# lmp9100.net
KiCad netlist of a schematic drawn in EAGLE
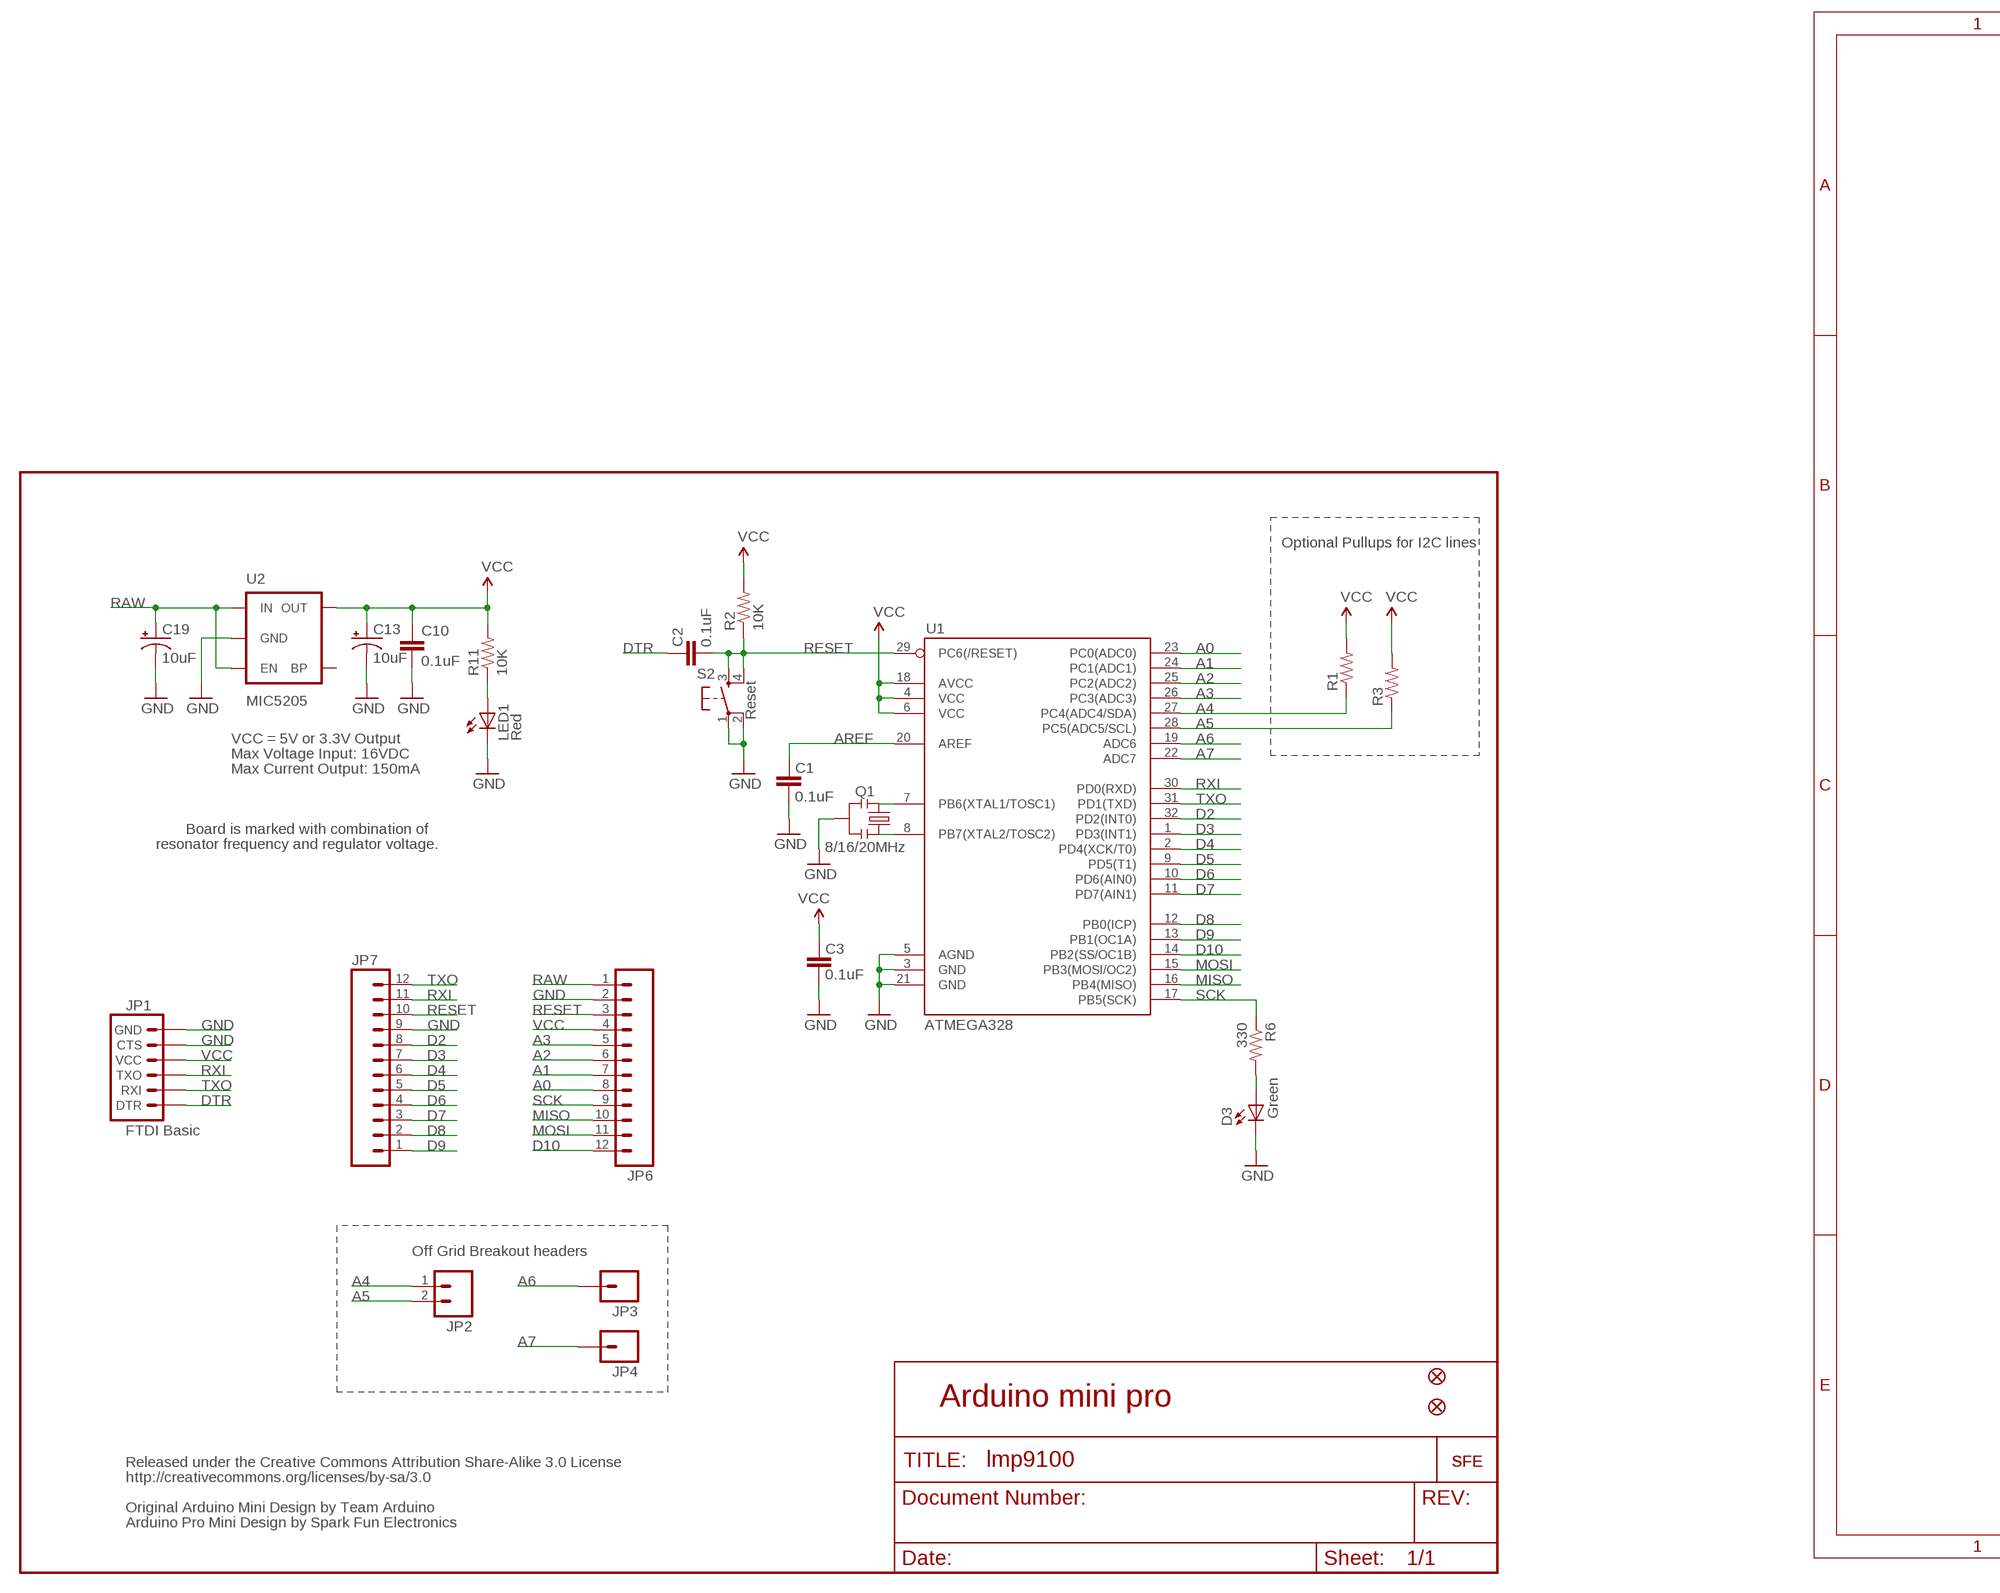
[diagram p0: schematic, sheet 1, part 1 of 2]
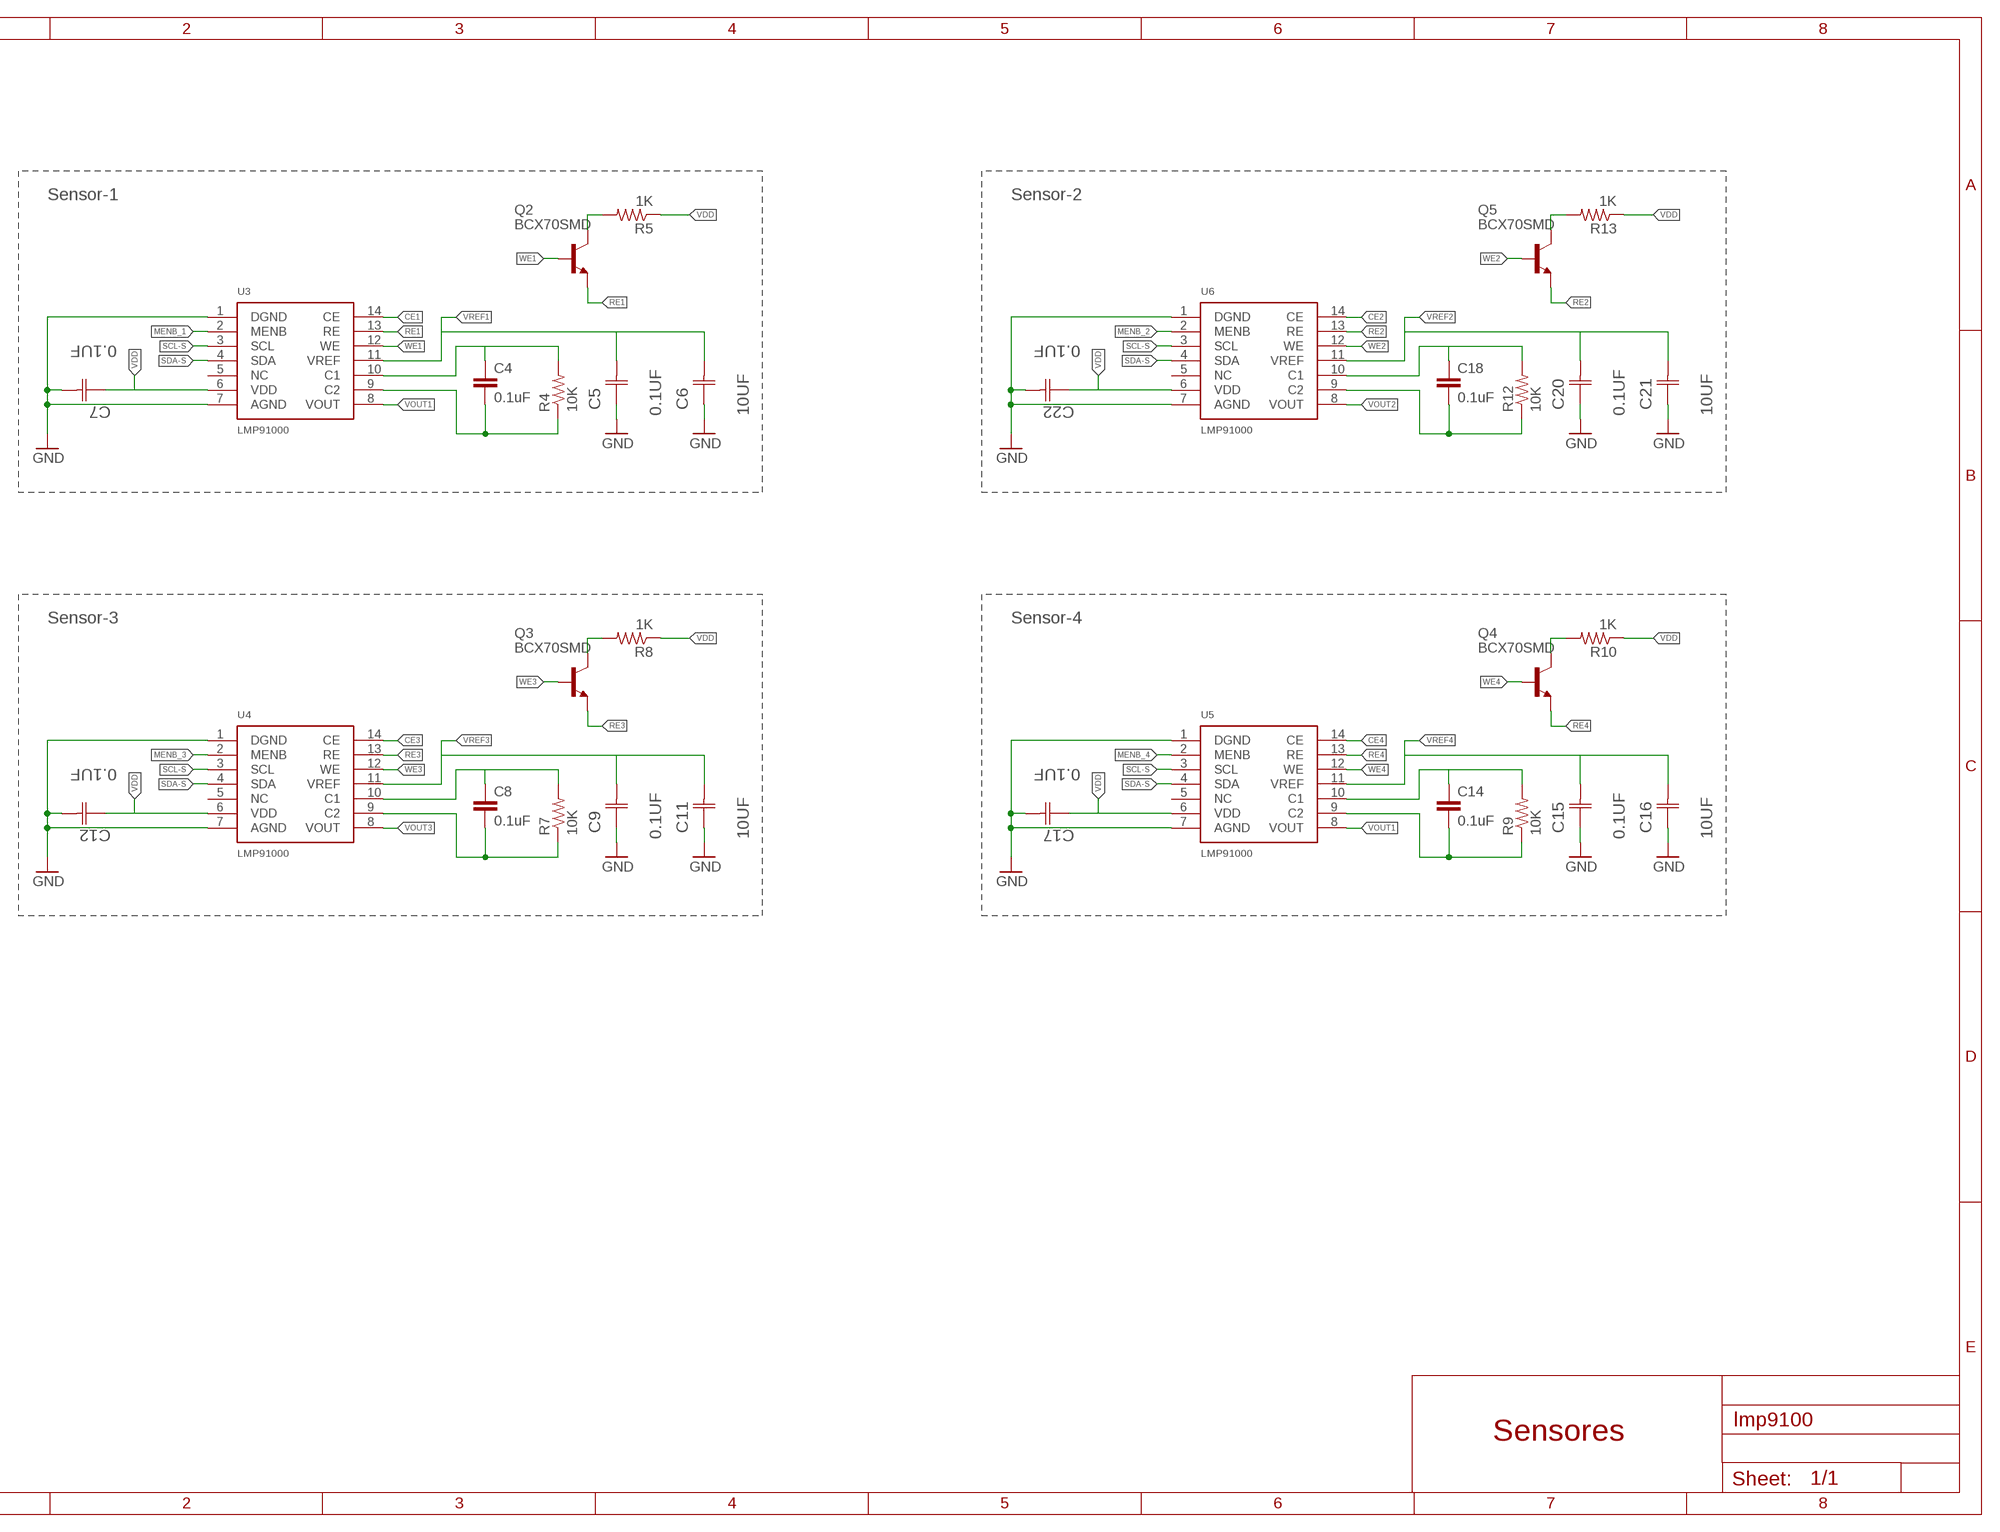
[diagram p1: schematic, sheet 1, part 2 of 2]

(export (version "E")
  (design (tool "Eeschema 10.0.6"))
  (components
    (comp (ref "C1")
      (value "0.1uF")
      (footprint "eagle-import:0402-CAP")
      (libsource (lib "eagle-import") (part "CAP0402-CAP"))
    )
    (comp (ref "C2")
      (value "0.1uF")
      (footprint "eagle-import:0402-CAP")
      (libsource (lib "eagle-import") (part "CAP0402-CAP"))
    )
    (comp (ref "C3")
      (value "0.1uF")
      (footprint "eagle-import:0402-CAP")
      (libsource (lib "eagle-import") (part "CAP0402-CAP"))
    )
    (comp (ref "C4")
      (value "0.1uF")
      (footprint "eagle-import:0402-CAP")
      (libsource (lib "eagle-import") (part "CAP0402-CAP"))
    )
    (comp (ref "C5")
      (value "0.1UF")
      (footprint "eagle-import:CAPC1608X90N")
      (fields (field (name "MPN") "0603YC104KAT2A") (field (name "TOLERANCE") "±10%"))
      (libsource (lib "eagle-import") (part "0603YC104KAT2A"))
    )
    (comp (ref "C6")
      (value "10UF")
      (footprint "eagle-import:CAPC3216X178N")
      (fields (field (name "MPN") "1206YD106MAT2A") (field (name "TOLERANCE") "±20%"))
      (libsource (lib "eagle-import") (part "1206YD106MAT2A"))
    )
    (comp (ref "C7")
      (value "0.1UF")
      (footprint "eagle-import:CAPC1608X90N")
      (fields (field (name "MPN") "0603YC104KAT2A") (field (name "TOLERANCE") "±10%"))
      (libsource (lib "eagle-import") (part "0603YC104KAT2A"))
    )
    (comp (ref "C8")
      (value "0.1uF")
      (footprint "eagle-import:0402-CAP")
      (libsource (lib "eagle-import") (part "CAP0402-CAP"))
    )
    (comp (ref "C9")
      (value "0.1UF")
      (footprint "eagle-import:CAPC1608X90N")
      (fields (field (name "MPN") "0603YC104KAT2A") (field (name "TOLERANCE") "±10%"))
      (libsource (lib "eagle-import") (part "0603YC104KAT2A"))
    )
    (comp (ref "C10")
      (value "0.1uF")
      (footprint "eagle-import:0402-CAP")
      (libsource (lib "eagle-import") (part "CAP0402-CAP"))
    )
    (comp (ref "C11")
      (value "10UF")
      (footprint "eagle-import:CAPC3216X178N")
      (fields (field (name "MPN") "1206YD106MAT2A") (field (name "TOLERANCE") "±20%"))
      (libsource (lib "eagle-import") (part "1206YD106MAT2A"))
    )
    (comp (ref "C12")
      (value "0.1UF")
      (footprint "eagle-import:CAPC1608X90N")
      (fields (field (name "MPN") "0603YC104KAT2A") (field (name "TOLERANCE") "±10%"))
      (libsource (lib "eagle-import") (part "0603YC104KAT2A"))
    )
    (comp (ref "C13")
      (value "10uF")
      (footprint "eagle-import:EIA3216")
      (libsource (lib "eagle-import") (part "CAP_POL1206"))
    )
    (comp (ref "C14")
      (value "0.1uF")
      (footprint "eagle-import:0402-CAP")
      (libsource (lib "eagle-import") (part "CAP0402-CAP"))
    )
    (comp (ref "C15")
      (value "0.1UF")
      (footprint "eagle-import:CAPC1608X90N")
      (fields (field (name "MPN") "0603YC104KAT2A") (field (name "TOLERANCE") "±10%"))
      (libsource (lib "eagle-import") (part "0603YC104KAT2A"))
    )
    (comp (ref "C16")
      (value "10UF")
      (footprint "eagle-import:CAPC3216X178N")
      (fields (field (name "MPN") "1206YD106MAT2A") (field (name "TOLERANCE") "±20%"))
      (libsource (lib "eagle-import") (part "1206YD106MAT2A"))
    )
    (comp (ref "C17")
      (value "0.1UF")
      (footprint "eagle-import:CAPC1608X90N")
      (fields (field (name "MPN") "0603YC104KAT2A") (field (name "TOLERANCE") "±10%"))
      (libsource (lib "eagle-import") (part "0603YC104KAT2A"))
    )
    (comp (ref "C18")
      (value "0.1uF")
      (footprint "eagle-import:0402-CAP")
      (libsource (lib "eagle-import") (part "CAP0402-CAP"))
    )
    (comp (ref "C19")
      (value "10uF")
      (footprint "eagle-import:EIA3216")
      (libsource (lib "eagle-import") (part "CAP_POL1206"))
    )
    (comp (ref "C20")
      (value "0.1UF")
      (footprint "eagle-import:CAPC1608X90N")
      (fields (field (name "MPN") "0603YC104KAT2A") (field (name "TOLERANCE") "±10%"))
      (libsource (lib "eagle-import") (part "0603YC104KAT2A"))
    )
    (comp (ref "C21")
      (value "10UF")
      (footprint "eagle-import:CAPC3216X178N")
      (fields (field (name "MPN") "1206YD106MAT2A") (field (name "TOLERANCE") "±20%"))
      (libsource (lib "eagle-import") (part "1206YD106MAT2A"))
    )
    (comp (ref "C22")
      (value "0.1UF")
      (footprint "eagle-import:CAPC1608X90N")
      (fields (field (name "MPN") "0603YC104KAT2A") (field (name "TOLERANCE") "±10%"))
      (libsource (lib "eagle-import") (part "0603YC104KAT2A"))
    )
    (comp (ref "D3")
      (value "Green")
      (footprint "eagle-import:LED-0603")
      (libsource (lib "eagle-import") (part "LED0603"))
    )
    (comp (ref "JP1")
      (value "FTDI Basic")
      (footprint "eagle-import:1X06")
      (libsource (lib "eagle-import") (part "ARDUINO_SERIAL_PROGRAMPTH"))
    )
    (comp (ref "JP2")
      (value "M02PTH")
      (footprint "eagle-import:1X02")
      (libsource (lib "eagle-import") (part "M02PTH"))
    )
    (comp (ref "JP3")
      (value "M01PTH")
      (footprint "eagle-import:1X01")
      (libsource (lib "eagle-import") (part "M01PTH"))
    )
    (comp (ref "JP4")
      (value "M01PTH")
      (footprint "eagle-import:1X01")
      (libsource (lib "eagle-import") (part "M01PTH"))
    )
    (comp (ref "JP5")
      (value "FIDUCIALUFIDUCIAL")
      (footprint "eagle-import:MICRO-FIDUCIAL")
      (libsource (lib "eagle-import") (part "FIDUCIALUFIDUCIAL"))
    )
    (comp (ref "JP6")
      (value "M12PTH")
      (footprint "eagle-import:1X12")
      (libsource (lib "eagle-import") (part "M12PTH"))
    )
    (comp (ref "JP7")
      (value "M12PTH")
      (footprint "eagle-import:1X12")
      (libsource (lib "eagle-import") (part "M12PTH"))
    )
    (comp (ref "JP8")
      (value "FIDUCIALUFIDUCIAL")
      (footprint "eagle-import:MICRO-FIDUCIAL")
      (libsource (lib "eagle-import") (part "FIDUCIALUFIDUCIAL"))
    )
    (comp (ref "LED1")
      (value "Red")
      (footprint "eagle-import:LED-0603")
      (libsource (lib "eagle-import") (part "LED0603"))
    )
    (comp (ref "Q1")
      (value "8/16/20MHz")
      (footprint "eagle-import:RESONATOR-SMD")
      (libsource (lib "eagle-import") (part "RESONATORSMD"))
    )
    (comp (ref "Q2")
      (value "BCX70SMD")
      (footprint "eagle-import:SOT23")
      (libsource (lib "eagle-import") (part "BCX70SMD"))
    )
    (comp (ref "Q3")
      (value "BCX70SMD")
      (footprint "eagle-import:SOT23")
      (libsource (lib "eagle-import") (part "BCX70SMD"))
    )
    (comp (ref "Q4")
      (value "BCX70SMD")
      (footprint "eagle-import:SOT23")
      (libsource (lib "eagle-import") (part "BCX70SMD"))
    )
    (comp (ref "Q5")
      (value "BCX70SMD")
      (footprint "eagle-import:SOT23")
      (libsource (lib "eagle-import") (part "BCX70SMD"))
    )
    (comp (ref "R1")
      (value "RESISTOR0402-RES")
      (footprint "eagle-import:0402-RES")
      (libsource (lib "eagle-import") (part "RESISTOR0402-RES"))
    )
    (comp (ref "R2")
      (value "10K")
      (footprint "eagle-import:0402-RES")
      (libsource (lib "eagle-import") (part "RESISTOR0402-RES"))
    )
    (comp (ref "R3")
      (value "RESISTOR0402-RES")
      (footprint "eagle-import:0402-RES")
      (libsource (lib "eagle-import") (part "RESISTOR0402-RES"))
    )
    (comp (ref "R4")
      (value "10K")
      (footprint "eagle-import:0402-RES")
      (libsource (lib "eagle-import") (part "RESISTOR0402-RES"))
    )
    (comp (ref "R5")
      (value "1K")
      (footprint "eagle-import:0402-RES")
      (libsource (lib "eagle-import") (part "RESISTOR0402-RES"))
    )
    (comp (ref "R6")
      (value "330")
      (footprint "eagle-import:0402-RES")
      (libsource (lib "eagle-import") (part "RESISTOR0402-RES"))
    )
    (comp (ref "R7")
      (value "10K")
      (footprint "eagle-import:0402-RES")
      (libsource (lib "eagle-import") (part "RESISTOR0402-RES"))
    )
    (comp (ref "R8")
      (value "1K")
      (footprint "eagle-import:0402-RES")
      (libsource (lib "eagle-import") (part "RESISTOR0402-RES"))
    )
    (comp (ref "R9")
      (value "10K")
      (footprint "eagle-import:0402-RES")
      (libsource (lib "eagle-import") (part "RESISTOR0402-RES"))
    )
    (comp (ref "R10")
      (value "1K")
      (footprint "eagle-import:0402-RES")
      (libsource (lib "eagle-import") (part "RESISTOR0402-RES"))
    )
    (comp (ref "R11")
      (value "10K")
      (footprint "eagle-import:0402-RES")
      (libsource (lib "eagle-import") (part "RESISTOR0402-RES"))
    )
    (comp (ref "R12")
      (value "10K")
      (footprint "eagle-import:0402-RES")
      (libsource (lib "eagle-import") (part "RESISTOR0402-RES"))
    )
    (comp (ref "R13")
      (value "1K")
      (footprint "eagle-import:0402-RES")
      (libsource (lib "eagle-import") (part "RESISTOR0402-RES"))
    )
    (comp (ref "S2")
      (value "Reset")
      (footprint "eagle-import:TACTILE_SWITCH_SMD")
      (libsource (lib "eagle-import") (part "TAC_SWITCHSMD"))
    )
    (comp (ref "U$1")
      (value "LOGO-SFESK")
      (footprint "eagle-import:SFE-LOGO-FLAME")
      (libsource (lib "eagle-import") (part "LOGO-SFESK"))
    )
    (comp (ref "U$11")
      (value "LOGO-SFENEW")
      (footprint "eagle-import:SFE-NEW-WEBLOGO")
      (libsource (lib "eagle-import") (part "LOGO-SFENEW"))
    )
    (comp (ref "U1")
      (value "ATMEGA328")
      (footprint "eagle-import:TQFP32-08")
      (libsource (lib "eagle-import") (part "ATMEGA168"))
    )
    (comp (ref "U2")
      (value "MIC5205")
      (footprint "eagle-import:SOT23-5")
      (libsource (lib "eagle-import") (part "V_REG_LDOSMD"))
    )
    (comp (ref "U3")
      (value "LMP91000")
      (footprint "eagle-import:LMP91000")
      (libsource (lib "eagle-import") (part "LMP91000"))
    )
    (comp (ref "U4")
      (value "LMP91000")
      (footprint "eagle-import:LMP91000")
      (libsource (lib "eagle-import") (part "LMP91000"))
    )
    (comp (ref "U5")
      (value "LMP91000")
      (footprint "eagle-import:LMP91000")
      (libsource (lib "eagle-import") (part "LMP91000"))
    )
    (comp (ref "U6")
      (value "LMP91000")
      (footprint "eagle-import:LMP91000")
      (libsource (lib "eagle-import") (part "LMP91000"))
    )
  )
  (nets
    (net (code "1") (name "/A0") (class "Default")
      (node (ref "JP6") (pin "8") (pinfunction "8_8") (pintype "passive"))
      (node (ref "U1") (pin "23") (pinfunction "PC0(ADC0)_23") (pintype "bidirectional"))
    )
    (net (code "2") (name "/A1") (class "Default")
      (node (ref "JP6") (pin "7") (pinfunction "7_7") (pintype "passive"))
      (node (ref "U1") (pin "24") (pinfunction "PC1(ADC1)_24") (pintype "bidirectional"))
    )
    (net (code "3") (name "/A2") (class "Default")
      (node (ref "JP6") (pin "6") (pinfunction "6_6") (pintype "passive"))
      (node (ref "U1") (pin "25") (pinfunction "PC2(ADC2)_25") (pintype "bidirectional"))
    )
    (net (code "4") (name "/A3") (class "Default")
      (node (ref "JP6") (pin "5") (pinfunction "5_5") (pintype "passive"))
      (node (ref "U1") (pin "26") (pinfunction "PC3(ADC3)_26") (pintype "bidirectional"))
    )
    (net (code "5") (name "/A4") (class "Default")
      (node (ref "JP2") (pin "1") (pinfunction "1_1") (pintype "passive"))
      (node (ref "R1") (pin "1") (pinfunction "1_1") (pintype "passive"))
      (node (ref "U1") (pin "27") (pinfunction "PC4(ADC4/SDA)_27") (pintype "bidirectional"))
    )
    (net (code "6") (name "/A5") (class "Default")
      (node (ref "JP2") (pin "2") (pinfunction "2_2") (pintype "passive"))
      (node (ref "R3") (pin "1") (pinfunction "1_1") (pintype "passive"))
      (node (ref "U1") (pin "28") (pinfunction "PC5(ADC5/SCL)_28") (pintype "bidirectional"))
    )
    (net (code "7") (name "/A6") (class "Default")
      (node (ref "JP3") (pin "1") (pinfunction "1_1") (pintype "passive"))
      (node (ref "U1") (pin "19") (pinfunction "ADC6_19") (pintype "bidirectional"))
    )
    (net (code "8") (name "/A7") (class "Default")
      (node (ref "JP4") (pin "1") (pinfunction "1_1") (pintype "passive"))
      (node (ref "U1") (pin "22") (pinfunction "ADC7_22") (pintype "bidirectional"))
    )
    (net (code "9") (name "/AREF") (class "Default")
      (node (ref "C1") (pin "2") (pinfunction "2_2") (pintype "passive"))
      (node (ref "U1") (pin "20") (pinfunction "AREF_20") (pintype "bidirectional"))
    )
    (net (code "10") (name "/D2") (class "Default")
      (node (ref "JP7") (pin "8") (pinfunction "8_8") (pintype "passive"))
      (node (ref "U1") (pin "32") (pinfunction "PD2(INT0)_32") (pintype "bidirectional"))
    )
    (net (code "11") (name "/D3") (class "Default")
      (node (ref "JP7") (pin "7") (pinfunction "7_7") (pintype "passive"))
      (node (ref "U1") (pin "1") (pinfunction "PD3(INT1)_1") (pintype "bidirectional"))
    )
    (net (code "12") (name "/D4") (class "Default")
      (node (ref "JP7") (pin "6") (pinfunction "6_6") (pintype "passive"))
      (node (ref "U1") (pin "2") (pinfunction "PD4(XCK/T0)_2") (pintype "bidirectional"))
    )
    (net (code "13") (name "/D5") (class "Default")
      (node (ref "JP7") (pin "5") (pinfunction "5_5") (pintype "passive"))
      (node (ref "U1") (pin "9") (pinfunction "PD5(T1)_9") (pintype "bidirectional"))
    )
    (net (code "14") (name "/D6") (class "Default")
      (node (ref "JP7") (pin "4") (pinfunction "4_4") (pintype "passive"))
      (node (ref "U1") (pin "10") (pinfunction "PD6(AIN0)_10") (pintype "bidirectional"))
    )
    (net (code "15") (name "/D7") (class "Default")
      (node (ref "JP7") (pin "3") (pinfunction "3_3") (pintype "passive"))
      (node (ref "U1") (pin "11") (pinfunction "PD7(AIN1)_11") (pintype "bidirectional"))
    )
    (net (code "16") (name "/D8") (class "Default")
      (node (ref "JP7") (pin "2") (pinfunction "2_2") (pintype "passive"))
      (node (ref "U1") (pin "12") (pinfunction "PB0(ICP)_12") (pintype "bidirectional"))
    )
    (net (code "17") (name "/D9") (class "Default")
      (node (ref "JP7") (pin "1") (pinfunction "1_1") (pintype "passive"))
      (node (ref "U1") (pin "13") (pinfunction "PB1(OC1A)_13") (pintype "bidirectional"))
    )
    (net (code "18") (name "/D10") (class "Default")
      (node (ref "JP6") (pin "12") (pinfunction "12_12") (pintype "passive"))
      (node (ref "U1") (pin "14") (pinfunction "PB2(SS/OC1B)_14") (pintype "bidirectional"))
    )
    (net (code "19") (name "/DTR") (class "Default")
      (node (ref "C2") (pin "2") (pinfunction "2_2") (pintype "passive"))
      (node (ref "JP1") (pin "1") (pinfunction "DTR_1") (pintype "passive"))
    )
    (net (code "20") (name "/MISO") (class "Default")
      (node (ref "JP6") (pin "10") (pinfunction "10_10") (pintype "passive"))
      (node (ref "U1") (pin "16") (pinfunction "PB4(MISO)_16") (pintype "bidirectional"))
    )
    (net (code "21") (name "/MOSI") (class "Default")
      (node (ref "JP6") (pin "11") (pinfunction "11_11") (pintype "passive"))
      (node (ref "U1") (pin "15") (pinfunction "PB3(MOSI/OC2)_15") (pintype "bidirectional"))
    )
    (net (code "22") (name "/RAW") (class "Default")
      (node (ref "C19") (pin "A") (pinfunction "+_A") (pintype "passive"))
      (node (ref "JP6") (pin "1") (pinfunction "1_1") (pintype "passive"))
      (node (ref "U2") (pin "1") (pinfunction "IN_1") (pintype "input"))
      (node (ref "U2") (pin "3") (pinfunction "EN_3") (pintype "input"))
    )
    (net (code "23") (name "/RESET") (class "Default")
      (node (ref "C2") (pin "1") (pinfunction "1_1") (pintype "passive"))
      (node (ref "JP6") (pin "3") (pinfunction "3_3") (pintype "passive"))
      (node (ref "JP7") (pin "10") (pinfunction "10_10") (pintype "passive"))
      (node (ref "R2") (pin "1") (pinfunction "1_1") (pintype "passive"))
      (node (ref "S2") (pin "3") (pinfunction "3_3") (pintype "passive"))
      (node (ref "S2") (pin "4") (pinfunction "4_4") (pintype "passive"))
      (node (ref "U1") (pin "29") (pinfunction "PC6(/RESET)_29") (pintype "bidirectional"))
    )
    (net (code "24") (name "/RXI") (class "Default")
      (node (ref "JP1") (pin "3") (pinfunction "TXO_3") (pintype "passive"))
      (node (ref "JP7") (pin "11") (pinfunction "11_11") (pintype "passive"))
      (node (ref "U1") (pin "30") (pinfunction "PD0(RXD)_30") (pintype "bidirectional"))
    )
    (net (code "25") (name "/SCK") (class "Default")
      (node (ref "JP6") (pin "9") (pinfunction "9_9") (pintype "passive"))
      (node (ref "R6") (pin "1") (pinfunction "1_1") (pintype "passive"))
      (node (ref "U1") (pin "17") (pinfunction "PB5(SCK)_17") (pintype "bidirectional"))
    )
    (net (code "26") (name "/TXO") (class "Default")
      (node (ref "JP1") (pin "2") (pinfunction "RXI_2") (pintype "passive"))
      (node (ref "JP7") (pin "12") (pinfunction "12_12") (pintype "passive"))
      (node (ref "U1") (pin "31") (pinfunction "PD1(TXD)_31") (pintype "bidirectional"))
    )
    (net (code "27") (name "CE1") (class "Default")
      (node (ref "U3") (pin "14") (pinfunction "CE_14") (pintype "bidirectional"))
    )
    (net (code "28") (name "CE2") (class "Default")
      (node (ref "U6") (pin "14") (pinfunction "CE_14") (pintype "bidirectional"))
    )
    (net (code "29") (name "CE3") (class "Default")
      (node (ref "U4") (pin "14") (pinfunction "CE_14") (pintype "bidirectional"))
    )
    (net (code "30") (name "CE4") (class "Default")
      (node (ref "U5") (pin "14") (pinfunction "CE_14") (pintype "bidirectional"))
    )
    (net (code "31") (name "GND") (class "Default")
      (node (ref "C1") (pin "1") (pinfunction "1_1") (pintype "passive"))
      (node (ref "C10") (pin "2") (pinfunction "2_2") (pintype "passive"))
      (node (ref "C11") (pin "1") (pinfunction "C1_1") (pintype "passive"))
      (node (ref "C12") (pin "2") (pinfunction "C2_2") (pintype "passive"))
      (node (ref "C13") (pin "C") (pinfunction "-_C") (pintype "passive"))
      (node (ref "C15") (pin "1") (pinfunction "C1_1") (pintype "passive"))
      (node (ref "C16") (pin "1") (pinfunction "C1_1") (pintype "passive"))
      (node (ref "C17") (pin "2") (pinfunction "C2_2") (pintype "passive"))
      (node (ref "C19") (pin "C") (pinfunction "-_C") (pintype "passive"))
      (node (ref "C20") (pin "1") (pinfunction "C1_1") (pintype "passive"))
      (node (ref "C21") (pin "1") (pinfunction "C1_1") (pintype "passive"))
      (node (ref "C22") (pin "2") (pinfunction "C2_2") (pintype "passive"))
      (node (ref "C3") (pin "1") (pinfunction "1_1") (pintype "passive"))
      (node (ref "C5") (pin "1") (pinfunction "C1_1") (pintype "passive"))
      (node (ref "C6") (pin "1") (pinfunction "C1_1") (pintype "passive"))
      (node (ref "C7") (pin "2") (pinfunction "C2_2") (pintype "passive"))
      (node (ref "C9") (pin "1") (pinfunction "C1_1") (pintype "passive"))
      (node (ref "D3") (pin "C") (pinfunction "C_C") (pintype "passive"))
      (node (ref "JP1") (pin "5") (pinfunction "CTS_5") (pintype "passive"))
      (node (ref "JP1") (pin "6") (pinfunction "GND_6") (pintype "passive"))
      (node (ref "JP6") (pin "2") (pinfunction "2_2") (pintype "passive"))
      (node (ref "JP7") (pin "9") (pinfunction "9_9") (pintype "passive"))
      (node (ref "LED1") (pin "C") (pinfunction "C_C") (pintype "passive"))
      (node (ref "Q1") (pin "2") (pinfunction "2_2") (pintype "passive"))
      (node (ref "S2") (pin "1") (pinfunction "1_1") (pintype "passive"))
      (node (ref "S2") (pin "2") (pinfunction "2_2") (pintype "passive"))
      (node (ref "U1") (pin "21") (pinfunction "GND_21") (pintype "bidirectional"))
      (node (ref "U1") (pin "3") (pinfunction "GND_3") (pintype "bidirectional"))
      (node (ref "U1") (pin "5") (pinfunction "AGND_5") (pintype "bidirectional"))
      (node (ref "U2") (pin "2") (pinfunction "GND_2") (pintype "input"))
      (node (ref "U3") (pin "1") (pinfunction "DGND_1") (pintype "bidirectional"))
      (node (ref "U3") (pin "7") (pinfunction "AGND_7") (pintype "bidirectional"))
      (node (ref "U4") (pin "1") (pinfunction "DGND_1") (pintype "bidirectional"))
      (node (ref "U4") (pin "7") (pinfunction "AGND_7") (pintype "bidirectional"))
      (node (ref "U5") (pin "1") (pinfunction "DGND_1") (pintype "bidirectional"))
      (node (ref "U5") (pin "7") (pinfunction "AGND_7") (pintype "bidirectional"))
      (node (ref "U6") (pin "1") (pinfunction "DGND_1") (pintype "bidirectional"))
      (node (ref "U6") (pin "7") (pinfunction "AGND_7") (pintype "bidirectional"))
    )
    (net (code "32") (name "MENB_1") (class "Default")
      (node (ref "U3") (pin "2") (pinfunction "MENB_2") (pintype "bidirectional"))
    )
    (net (code "33") (name "MENB_2") (class "Default")
      (node (ref "U6") (pin "2") (pinfunction "MENB_2") (pintype "bidirectional"))
    )
    (net (code "34") (name "MENB_3") (class "Default")
      (node (ref "U4") (pin "2") (pinfunction "MENB_2") (pintype "bidirectional"))
    )
    (net (code "35") (name "MENB_4") (class "Default")
      (node (ref "U5") (pin "2") (pinfunction "MENB_2") (pintype "bidirectional"))
    )
    (net (code "36") (name "Net-(D3-PadA)") (class "Default")
      (node (ref "D3") (pin "A") (pinfunction "A_A") (pintype "passive"))
      (node (ref "R6") (pin "2") (pinfunction "2_2") (pintype "passive"))
    )
    (net (code "37") (name "Net-(LED1-PadA)") (class "Default")
      (node (ref "LED1") (pin "A") (pinfunction "A_A") (pintype "passive"))
      (node (ref "R11") (pin "1") (pinfunction "1_1") (pintype "passive"))
    )
    (net (code "38") (name "Net-(Q2-C)") (class "Default")
      (node (ref "Q2") (pin "3") (pinfunction "C_3") (pintype "passive"))
      (node (ref "R5") (pin "2") (pinfunction "2_2") (pintype "passive"))
    )
    (net (code "39") (name "Net-(Q3-C)") (class "Default")
      (node (ref "Q3") (pin "3") (pinfunction "C_3") (pintype "passive"))
      (node (ref "R8") (pin "2") (pinfunction "2_2") (pintype "passive"))
    )
    (net (code "40") (name "Net-(Q4-C)") (class "Default")
      (node (ref "Q4") (pin "3") (pinfunction "C_3") (pintype "passive"))
      (node (ref "R10") (pin "2") (pinfunction "2_2") (pintype "passive"))
    )
    (net (code "41") (name "Net-(Q5-C)") (class "Default")
      (node (ref "Q5") (pin "3") (pinfunction "C_3") (pintype "passive"))
      (node (ref "R13") (pin "2") (pinfunction "2_2") (pintype "passive"))
    )
    (net (code "42") (name "Net-(U1-PB6(XTAL1{slash}TOSC1))") (class "Default")
      (node (ref "Q1") (pin "3") (pinfunction "3_3") (pintype "passive"))
      (node (ref "U1") (pin "7") (pinfunction "PB6(XTAL1/TOSC1)_7") (pintype "bidirectional"))
    )
    (net (code "43") (name "Net-(U1-PB7(XTAL2{slash}TOSC2))") (class "Default")
      (node (ref "Q1") (pin "1") (pinfunction "1_1") (pintype "passive"))
      (node (ref "U1") (pin "8") (pinfunction "PB7(XTAL2/TOSC2)_8") (pintype "bidirectional"))
    )
    (net (code "44") (name "Net-(U3-C1)") (class "Default")
      (node (ref "C4") (pin "1") (pinfunction "1_1") (pintype "passive"))
      (node (ref "R4") (pin "2") (pinfunction "2_2") (pintype "passive"))
      (node (ref "U3") (pin "10") (pinfunction "C1_10") (pintype "bidirectional"))
    )
    (net (code "45") (name "Net-(U3-C2)") (class "Default")
      (node (ref "C4") (pin "2") (pinfunction "2_2") (pintype "passive"))
      (node (ref "R4") (pin "1") (pinfunction "1_1") (pintype "passive"))
      (node (ref "U3") (pin "9") (pinfunction "C2_9") (pintype "bidirectional"))
    )
    (net (code "46") (name "Net-(U4-C1)") (class "Default")
      (node (ref "C8") (pin "1") (pinfunction "1_1") (pintype "passive"))
      (node (ref "R7") (pin "2") (pinfunction "2_2") (pintype "passive"))
      (node (ref "U4") (pin "10") (pinfunction "C1_10") (pintype "bidirectional"))
    )
    (net (code "47") (name "Net-(U4-C2)") (class "Default")
      (node (ref "C8") (pin "2") (pinfunction "2_2") (pintype "passive"))
      (node (ref "R7") (pin "1") (pinfunction "1_1") (pintype "passive"))
      (node (ref "U4") (pin "9") (pinfunction "C2_9") (pintype "bidirectional"))
    )
    (net (code "48") (name "Net-(U5-C1)") (class "Default")
      (node (ref "C14") (pin "1") (pinfunction "1_1") (pintype "passive"))
      (node (ref "R9") (pin "2") (pinfunction "2_2") (pintype "passive"))
      (node (ref "U5") (pin "10") (pinfunction "C1_10") (pintype "bidirectional"))
    )
    (net (code "49") (name "Net-(U5-C2)") (class "Default")
      (node (ref "C14") (pin "2") (pinfunction "2_2") (pintype "passive"))
      (node (ref "R9") (pin "1") (pinfunction "1_1") (pintype "passive"))
      (node (ref "U5") (pin "9") (pinfunction "C2_9") (pintype "bidirectional"))
    )
    (net (code "50") (name "Net-(U6-C1)") (class "Default")
      (node (ref "C18") (pin "1") (pinfunction "1_1") (pintype "passive"))
      (node (ref "R12") (pin "2") (pinfunction "2_2") (pintype "passive"))
      (node (ref "U6") (pin "10") (pinfunction "C1_10") (pintype "bidirectional"))
    )
    (net (code "51") (name "Net-(U6-C2)") (class "Default")
      (node (ref "C18") (pin "2") (pinfunction "2_2") (pintype "passive"))
      (node (ref "R12") (pin "1") (pinfunction "1_1") (pintype "passive"))
      (node (ref "U6") (pin "9") (pinfunction "C2_9") (pintype "bidirectional"))
    )
    (net (code "52") (name "RE1") (class "Default")
      (node (ref "Q2") (pin "2") (pinfunction "E_2") (pintype "passive"))
      (node (ref "U3") (pin "13") (pinfunction "RE_13") (pintype "bidirectional"))
    )
    (net (code "53") (name "RE2") (class "Default")
      (node (ref "Q5") (pin "2") (pinfunction "E_2") (pintype "passive"))
      (node (ref "U6") (pin "13") (pinfunction "RE_13") (pintype "bidirectional"))
    )
    (net (code "54") (name "RE3") (class "Default")
      (node (ref "Q3") (pin "2") (pinfunction "E_2") (pintype "passive"))
      (node (ref "U4") (pin "13") (pinfunction "RE_13") (pintype "bidirectional"))
    )
    (net (code "55") (name "RE4") (class "Default")
      (node (ref "Q4") (pin "2") (pinfunction "E_2") (pintype "passive"))
      (node (ref "U5") (pin "13") (pinfunction "RE_13") (pintype "bidirectional"))
    )
    (net (code "56") (name "SCL-S") (class "Default")
      (node (ref "U3") (pin "3") (pinfunction "SCL_3") (pintype "bidirectional"))
      (node (ref "U4") (pin "3") (pinfunction "SCL_3") (pintype "bidirectional"))
      (node (ref "U5") (pin "3") (pinfunction "SCL_3") (pintype "bidirectional"))
      (node (ref "U6") (pin "3") (pinfunction "SCL_3") (pintype "bidirectional"))
    )
    (net (code "57") (name "SDA-S") (class "Default")
      (node (ref "U3") (pin "4") (pinfunction "SDA_4") (pintype "bidirectional"))
      (node (ref "U4") (pin "4") (pinfunction "SDA_4") (pintype "bidirectional"))
      (node (ref "U5") (pin "4") (pinfunction "SDA_4") (pintype "bidirectional"))
      (node (ref "U6") (pin "4") (pinfunction "SDA_4") (pintype "bidirectional"))
    )
    (net (code "58") (name "VCC") (class "Default")
      (node (ref "C10") (pin "1") (pinfunction "1_1") (pintype "passive"))
      (node (ref "C13") (pin "A") (pinfunction "+_A") (pintype "passive"))
      (node (ref "C3") (pin "2") (pinfunction "2_2") (pintype "passive"))
      (node (ref "JP1") (pin "4") (pinfunction "VCC_4") (pintype "passive"))
      (node (ref "JP6") (pin "4") (pinfunction "4_4") (pintype "passive"))
      (node (ref "R1") (pin "2") (pinfunction "2_2") (pintype "passive"))
      (node (ref "R11") (pin "2") (pinfunction "2_2") (pintype "passive"))
      (node (ref "R2") (pin "2") (pinfunction "2_2") (pintype "passive"))
      (node (ref "R3") (pin "2") (pinfunction "2_2") (pintype "passive"))
      (node (ref "U1") (pin "18") (pinfunction "AVCC_18") (pintype "bidirectional"))
      (node (ref "U1") (pin "4") (pinfunction "VCC_4") (pintype "bidirectional"))
      (node (ref "U1") (pin "6") (pinfunction "VCC_6") (pintype "bidirectional"))
      (node (ref "U2") (pin "5") (pinfunction "OUT_5") (pintype "passive"))
    )
    (net (code "59") (name "VDD") (class "Default")
      (node (ref "C12") (pin "1") (pinfunction "C1_1") (pintype "passive"))
      (node (ref "C17") (pin "1") (pinfunction "C1_1") (pintype "passive"))
      (node (ref "C22") (pin "1") (pinfunction "C1_1") (pintype "passive"))
      (node (ref "C7") (pin "1") (pinfunction "C1_1") (pintype "passive"))
      (node (ref "R10") (pin "1") (pinfunction "1_1") (pintype "passive"))
      (node (ref "R13") (pin "1") (pinfunction "1_1") (pintype "passive"))
      (node (ref "R5") (pin "1") (pinfunction "1_1") (pintype "passive"))
      (node (ref "R8") (pin "1") (pinfunction "1_1") (pintype "passive"))
      (node (ref "U3") (pin "6") (pinfunction "VDD_6") (pintype "bidirectional"))
      (node (ref "U4") (pin "6") (pinfunction "VDD_6") (pintype "bidirectional"))
      (node (ref "U5") (pin "6") (pinfunction "VDD_6") (pintype "bidirectional"))
      (node (ref "U6") (pin "6") (pinfunction "VDD_6") (pintype "bidirectional"))
    )
    (net (code "60") (name "VOUT1") (class "Default")
      (node (ref "U3") (pin "8") (pinfunction "VOUT_8") (pintype "bidirectional"))
      (node (ref "U5") (pin "8") (pinfunction "VOUT_8") (pintype "bidirectional"))
    )
    (net (code "61") (name "VOUT2") (class "Default")
      (node (ref "U6") (pin "8") (pinfunction "VOUT_8") (pintype "bidirectional"))
    )
    (net (code "62") (name "VOUT3") (class "Default")
      (node (ref "U4") (pin "8") (pinfunction "VOUT_8") (pintype "bidirectional"))
    )
    (net (code "63") (name "VREF1") (class "Default")
      (node (ref "C5") (pin "2") (pinfunction "C2_2") (pintype "passive"))
      (node (ref "C6") (pin "2") (pinfunction "C2_2") (pintype "passive"))
      (node (ref "U3") (pin "11") (pinfunction "VREF_11") (pintype "bidirectional"))
    )
    (net (code "64") (name "VREF2") (class "Default")
      (node (ref "C20") (pin "2") (pinfunction "C2_2") (pintype "passive"))
      (node (ref "C21") (pin "2") (pinfunction "C2_2") (pintype "passive"))
      (node (ref "U6") (pin "11") (pinfunction "VREF_11") (pintype "bidirectional"))
    )
    (net (code "65") (name "VREF3") (class "Default")
      (node (ref "C11") (pin "2") (pinfunction "C2_2") (pintype "passive"))
      (node (ref "C9") (pin "2") (pinfunction "C2_2") (pintype "passive"))
      (node (ref "U4") (pin "11") (pinfunction "VREF_11") (pintype "bidirectional"))
    )
    (net (code "66") (name "VREF4") (class "Default")
      (node (ref "C15") (pin "2") (pinfunction "C2_2") (pintype "passive"))
      (node (ref "C16") (pin "2") (pinfunction "C2_2") (pintype "passive"))
      (node (ref "U5") (pin "11") (pinfunction "VREF_11") (pintype "bidirectional"))
    )
    (net (code "67") (name "WE1") (class "Default")
      (node (ref "Q2") (pin "1") (pinfunction "B_1") (pintype "passive"))
      (node (ref "U3") (pin "12") (pinfunction "WE_12") (pintype "bidirectional"))
    )
    (net (code "68") (name "WE2") (class "Default")
      (node (ref "Q5") (pin "1") (pinfunction "B_1") (pintype "passive"))
      (node (ref "U6") (pin "12") (pinfunction "WE_12") (pintype "bidirectional"))
    )
    (net (code "69") (name "WE3") (class "Default")
      (node (ref "Q3") (pin "1") (pinfunction "B_1") (pintype "passive"))
      (node (ref "U4") (pin "12") (pinfunction "WE_12") (pintype "bidirectional"))
    )
    (net (code "70") (name "WE4") (class "Default")
      (node (ref "Q4") (pin "1") (pinfunction "B_1") (pintype "passive"))
      (node (ref "U5") (pin "12") (pinfunction "WE_12") (pintype "bidirectional"))
    )
    (net (code "71") (name "unconnected-(U2-BP-Pad4)") (class "Default")
      (node (ref "U2") (pin "4") (pinfunction "BP_4") (pintype "input"))
    )
    (net (code "72") (name "unconnected-(U3-NC-Pad5)") (class "Default")
      (node (ref "U3") (pin "5") (pinfunction "NC_5") (pintype "bidirectional"))
    )
    (net (code "73") (name "unconnected-(U4-NC-Pad5)") (class "Default")
      (node (ref "U4") (pin "5") (pinfunction "NC_5") (pintype "bidirectional"))
    )
    (net (code "74") (name "unconnected-(U5-NC-Pad5)") (class "Default")
      (node (ref "U5") (pin "5") (pinfunction "NC_5") (pintype "bidirectional"))
    )
    (net (code "75") (name "unconnected-(U6-NC-Pad5)") (class "Default")
      (node (ref "U6") (pin "5") (pinfunction "NC_5") (pintype "bidirectional"))
    )
  )
)
